# expansion_port.net
KiCad netlist of a schematic drawn in Altium Designer
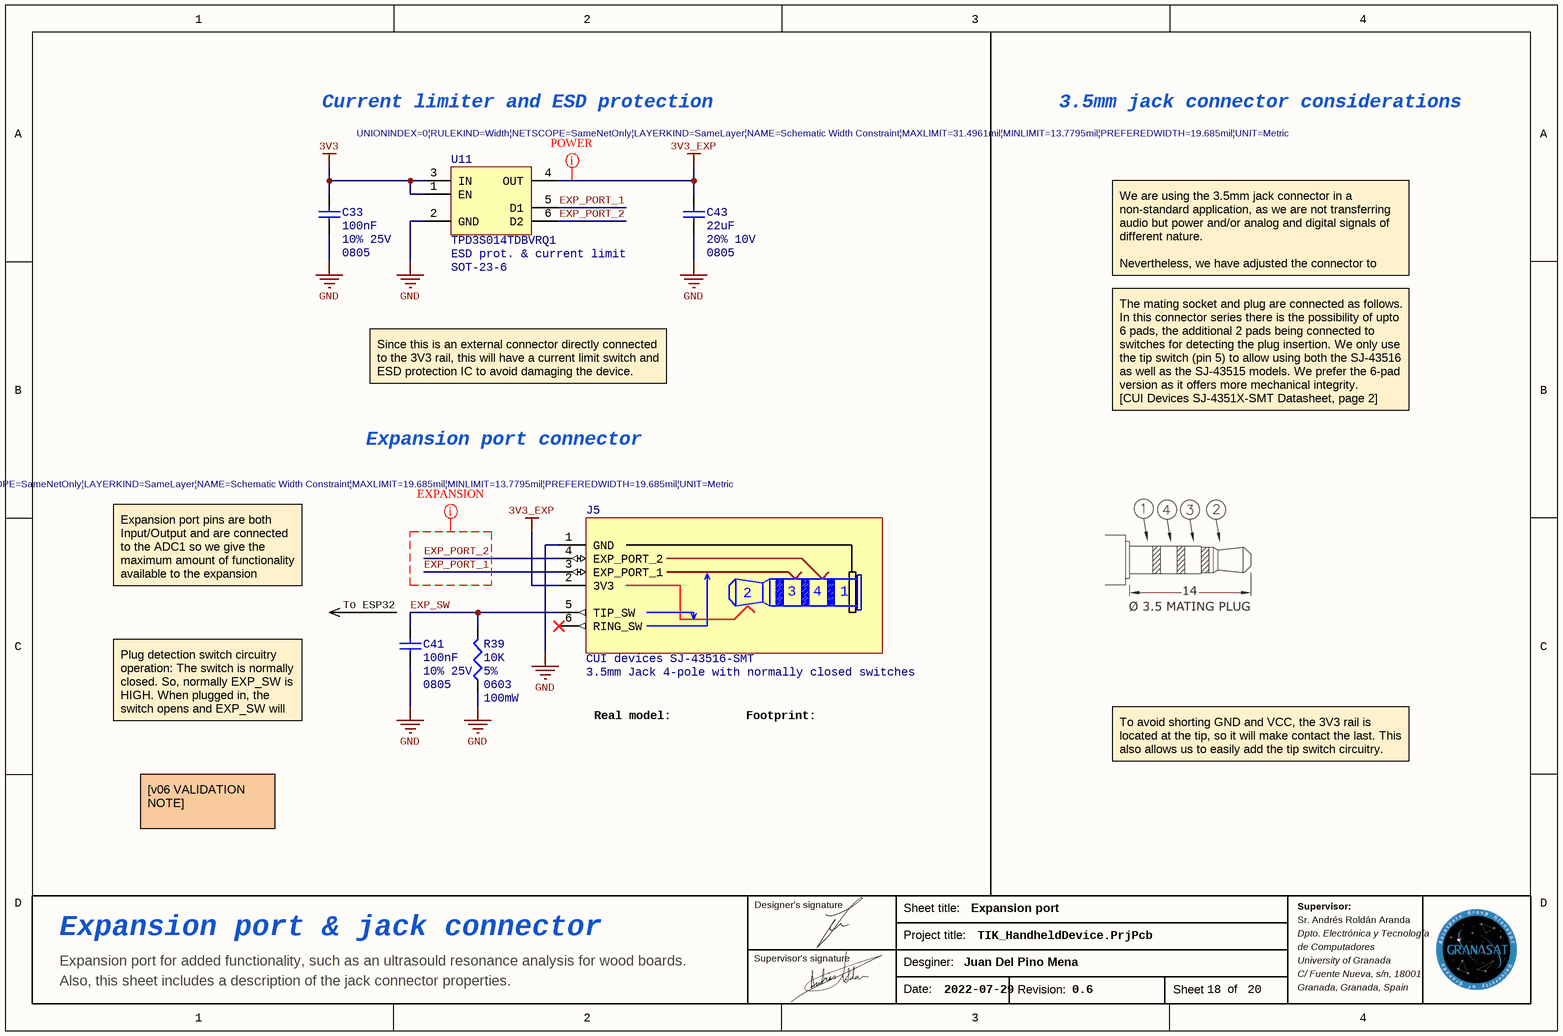
[diagram p0: expansion_port.SchDoc]

(export (version "E")
  (design (tool "Eeschema 10.0.6"))
  (components
    (comp (ref "C33")
      (value "100nF")
      (footprint "CAP 0805_2012")
      (description "Ceramic cap size 0805")
      (fields
        (field (name "TOLERANCE") "10% 25V")
        (field (name "PACKAGEDESCRIPTION") "0805")
        (field (name "Comment") "Cap_cer_0805")
      )
      (libsource (lib "tik_handheld_schlib") (part "Cap_cer_0805_100nF_10%"))
    )
    (comp (ref "C41")
      (value "100nF")
      (footprint "CAP 0805_2012")
      (description "Ceramic cap size 0805")
      (fields
        (field (name "TOLERANCE") "10% 25V")
        (field (name "PACKAGEDESCRIPTION") "0805")
        (field (name "Comment") "Cap_cer_0805")
      )
      (libsource (lib "tik_handheld_schlib") (part "Cap_cer_0805_100nF_10%"))
    )
    (comp (ref "C43")
      (value "22uF")
      (footprint "CAP 0805_2012")
      (description "Ceramic cap size 0805 CC0805MKX5R6BB226 Yageo MLCC 22uF 10V 20% X5R")
      (fields
        (field (name "TOLERANCE") "20% 10V")
        (field (name "PACKAGEDESCRIPTION") "0805")
        (field (name "Comment") "Cap_cer_0805")
      )
      (libsource (lib "tik_handheld_schlib") (part "Cap_cer_0805_22uF_20%"))
    )
    (comp (ref "J5")
      (value "CON EXPANSION_PORT")
      (footprint "JACK_6_CONN_CUI_DEVICES_SJ-43516-SMT")
      (description "3.5mm Jack 4-pole with normally closed switches")
      (fields
        (field (name "DESC") "3.5mm Jack 4-pole with normally closed switches")
        (field (name "PART") "CUI devices SJ-43516-SMT")
      )
      (libsource (lib "tik_handheld_schlib") (part "CON EXPANSION_PORT"))
    )
    (comp (ref "R39")
      (value "10K")
      (footprint "RES 0603_1608")
      (description "Res size 0603 SMD mounting, low power")
      (fields
        (field (name "TOLERANCE") "5%")
        (field (name "PACKAGEDESCRIPTION") "0603")
        (field (name "POWERDISIPATED") "100mW")
        (field (name "Comment") "Res_0603_10K_5%_100mW_1")
      )
      (libsource (lib "tik_handheld_schlib") (part "Res_0603_10K_5%_100mW_1"))
    )
    (comp (ref "U11")
      (value "IC TPD3S014 Current switch")
      (footprint "TSOT-23-6 TPD3S014TDBVRQ1")
      (description "TPD3S014TDBVRQ1 ESD prot. & current limit")
      (fields
        (field (name "PART") "TPD3S014TDBVRQ1")
        (field (name "PACKAGEDESCRIPTION") "SOT-23-6")
        (field (name "DESC") "ESD prot. & current limit")
      )
      (libsource (lib "tik_handheld_schlib") (part "IC TPD3S014 Current switch"))
    )
  )
  (nets
    (net (code "1") (name "/EXP_PORT_1") (class "Default")
      (node (ref "J5") (pin "3") (pinfunction "EXP_PORT_1_3") (pintype "bidirectional"))
      (node (ref "U11") (pin "5") (pinfunction "D1_5") (pintype "passive"))
    )
    (net (code "2") (name "/EXP_PORT_2") (class "Default")
      (node (ref "J5") (pin "4") (pinfunction "EXP_PORT_2_4") (pintype "bidirectional"))
      (node (ref "U11") (pin "6") (pinfunction "D2_6") (pintype "passive"))
    )
    (net (code "3") (name "/EXP_SW") (class "Default")
      (node (ref "C41") (pin "2") (pinfunction "2_2") (pintype "passive"))
      (node (ref "J5") (pin "5") (pinfunction "TIP_SW_5") (pintype "output"))
      (node (ref "R39") (pin "2") (pinfunction "2_2") (pintype "passive"))
    )
    (net (code "4") (name "3V3") (class "Default")
      (node (ref "C33") (pin "2") (pinfunction "2_2") (pintype "passive"))
      (node (ref "U11") (pin "1") (pinfunction "EN_1") (pintype "passive"))
      (node (ref "U11") (pin "3") (pinfunction "IN_3") (pintype "passive"))
    )
    (net (code "5") (name "3V3_EXP") (class "Default")
      (node (ref "C43") (pin "2") (pinfunction "2_2") (pintype "passive"))
      (node (ref "J5") (pin "2") (pinfunction "3V3_2") (pintype "power_in"))
      (node (ref "U11") (pin "4") (pinfunction "OUT_4") (pintype "passive"))
    )
    (net (code "6") (name "GND") (class "Default")
      (node (ref "C33") (pin "1") (pinfunction "1_1") (pintype "passive"))
      (node (ref "C41") (pin "1") (pinfunction "1_1") (pintype "passive"))
      (node (ref "C43") (pin "1") (pinfunction "1_1") (pintype "passive"))
      (node (ref "J5") (pin "1") (pinfunction "GND_1") (pintype "power_in"))
      (node (ref "R39") (pin "1") (pinfunction "1_1") (pintype "passive"))
      (node (ref "U11") (pin "2") (pinfunction "GND_2") (pintype "passive"))
    )
    (net (code "7") (name "unconnected-(J5-RING_SW-Pad6)") (class "Default")
      (node (ref "J5") (pin "6") (pinfunction "RING_SW_6") (pintype "output+no_connect"))
    )
  )
)
